# PIC32Square.net
KiCad netlist of a schematic drawn in Altium Designer
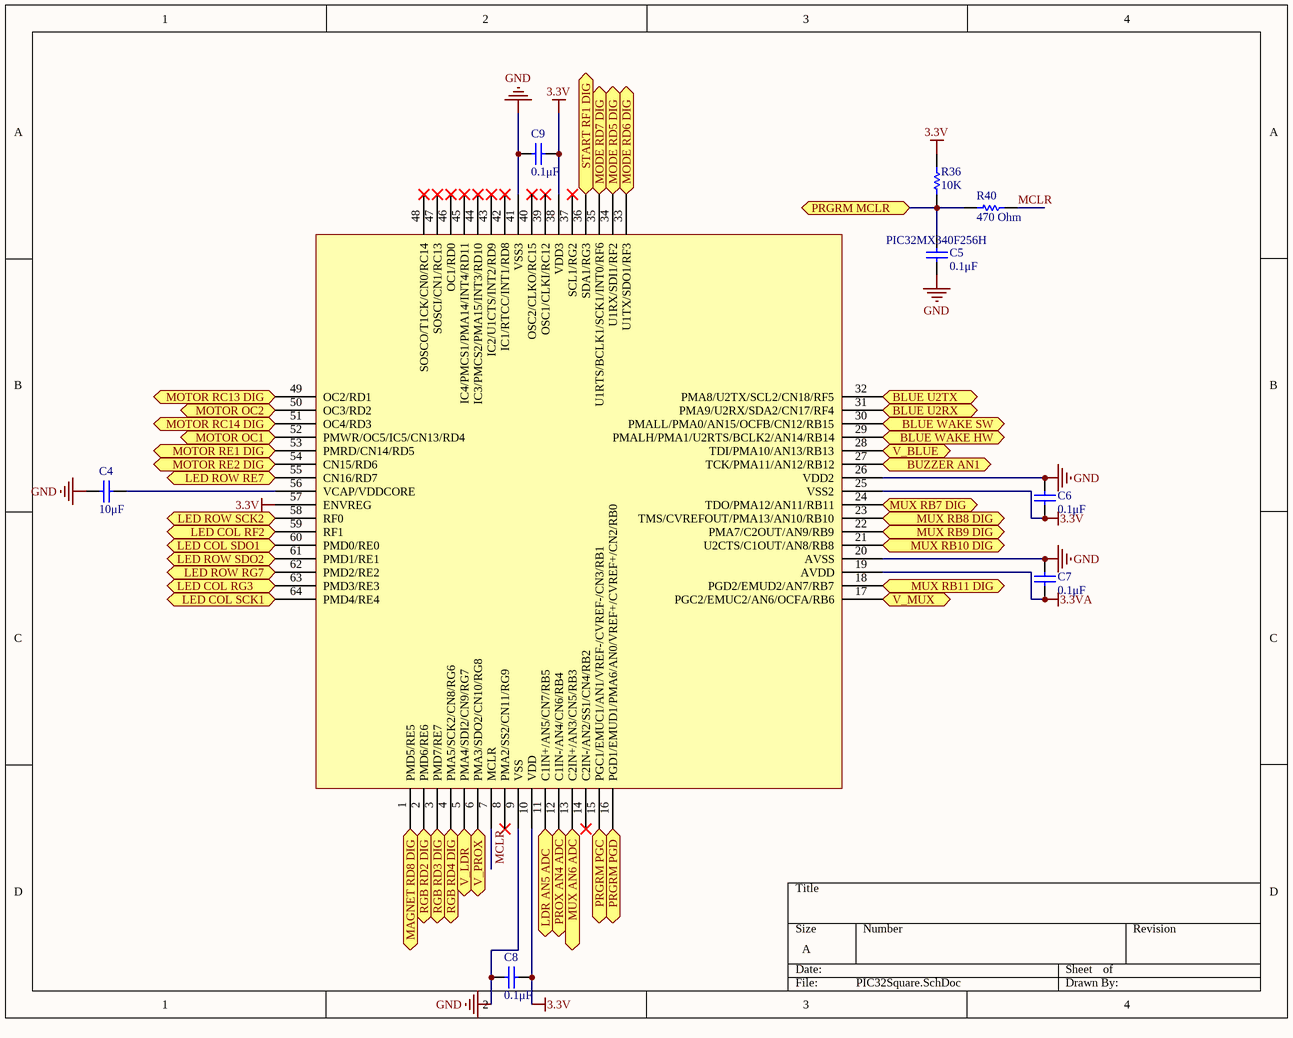
[diagram p0: PIC32Square.SchDoc]

(export (version "E")
  (design (tool "Eeschema 10.0.6"))
  (components
    (comp (ref "C4")
      (value "10μF")
      (footprint "Capacitor")
      (description "Capacitor")
      (fields (field (name "PUBLISHER") "Altium Limited"))
      (libsource (lib "Miscellaneous Devices") (part "Cap"))
    )
    (comp (ref "C5")
      (value "0.1μF")
      (footprint "Capacitor")
      (description "Capacitor")
      (fields (field (name "PUBLISHER") "Altium Limited"))
      (libsource (lib "Miscellaneous Devices") (part "Cap"))
    )
    (comp (ref "C6")
      (value "0.1μF")
      (footprint "Capacitor")
      (description "Capacitor")
      (fields (field (name "PUBLISHER") "Altium Limited"))
      (libsource (lib "Miscellaneous Devices") (part "Cap"))
    )
    (comp (ref "C7")
      (value "0.1μF")
      (footprint "Capacitor")
      (description "Capacitor")
      (fields (field (name "PUBLISHER") "Altium Limited"))
      (libsource (lib "Miscellaneous Devices") (part "Cap"))
    )
    (comp (ref "C8")
      (value "0.1μF")
      (footprint "Capacitor")
      (description "Capacitor")
      (fields (field (name "PUBLISHER") "Altium Limited"))
      (libsource (lib "Miscellaneous Devices") (part "Cap"))
    )
    (comp (ref "C9")
      (value "0.1μF")
      (footprint "Capacitor")
      (description "Capacitor")
      (fields (field (name "PUBLISHER") "Altium Limited"))
      (libsource (lib "Miscellaneous Devices") (part "Cap"))
    )
    (comp (ref "PIC32Square")
      (value "PIC32MX340F256H")
      (footprint "PIC32")
      (libsource (lib "PROBOT_Schema_Library") (part "PIC32square"))
    )
    (comp (ref "R36")
      (value "10K")
      (footprint "Resistor0603")
      (description "Resistor")
      (fields (field (name "PUBLISHER") "Altium Limited"))
      (libsource (lib "Miscellaneous Devices") (part "Res1"))
    )
    (comp (ref "R40")
      (value "470 Ohm")
      (footprint "Resistor0603")
      (description "Resistor")
      (fields (field (name "PUBLISHER") "Altium Limited"))
      (libsource (lib "Miscellaneous Devices") (part "Res1"))
    )
  )
  (nets
    (net (code "1") (name "/BLUE U2RX") (class "Default")
      (node (ref "PIC32Square") (pin "31") (pinfunction "PMA9/U2RX/SDA2/CN17/RF4_31") (pintype "passive"))
    )
    (net (code "2") (name "/BLUE U2TX") (class "Default")
      (node (ref "PIC32Square") (pin "32") (pinfunction "PMA8/U2TX/SCL2/CN18/RF5_32") (pintype "passive"))
    )
    (net (code "3") (name "/BLUE WAKE HW") (class "Default")
      (node (ref "PIC32Square") (pin "29") (pinfunction "PMALH/PMA1/U2RTS/BCLK2/AN14/RB14_29") (pintype "passive"))
    )
    (net (code "4") (name "/BLUE WAKE SW") (class "Default")
      (node (ref "PIC32Square") (pin "30") (pinfunction "PMALL/PMA0/AN15/OCFB/CN12/RB15_30") (pintype "passive"))
    )
    (net (code "5") (name "/BUZZER AN1") (class "Default")
      (node (ref "PIC32Square") (pin "27") (pinfunction "TCK/PMA11/AN12/RB12_27") (pintype "passive"))
    )
    (net (code "6") (name "/LDR AN5 ADC") (class "Default")
      (node (ref "PIC32Square") (pin "11") (pinfunction "C1IN+/AN5/CN7/RB5_11") (pintype "passive"))
    )
    (net (code "7") (name "/LED COL RF2") (class "Default")
      (node (ref "PIC32Square") (pin "59") (pinfunction "RF1_59") (pintype "passive"))
    )
    (net (code "8") (name "/LED COL RG3") (class "Default")
      (node (ref "PIC32Square") (pin "63") (pinfunction "PMD3/RE3_63") (pintype "passive"))
    )
    (net (code "9") (name "/LED COL SCK1") (class "Default")
      (node (ref "PIC32Square") (pin "64") (pinfunction "PMD4/RE4_64") (pintype "passive"))
    )
    (net (code "10") (name "/LED COL SDO1") (class "Default")
      (node (ref "PIC32Square") (pin "60") (pinfunction "PMD0/RE0_60") (pintype "passive"))
    )
    (net (code "11") (name "/LED ROW RE7") (class "Default")
      (node (ref "PIC32Square") (pin "55") (pinfunction "CN16/RD7_55") (pintype "passive"))
    )
    (net (code "12") (name "/LED ROW RG7") (class "Default")
      (node (ref "PIC32Square") (pin "62") (pinfunction "PMD2/RE2_62") (pintype "passive"))
    )
    (net (code "13") (name "/LED ROW SCK2") (class "Default")
      (node (ref "PIC32Square") (pin "58") (pinfunction "RF0_58") (pintype "passive"))
    )
    (net (code "14") (name "/LED ROW SDO2") (class "Default")
      (node (ref "PIC32Square") (pin "61") (pinfunction "PMD1/RE1_61") (pintype "passive"))
    )
    (net (code "15") (name "/MAGNET RD8 DIG") (class "Default")
      (node (ref "PIC32Square") (pin "1") (pinfunction "PMD5/RE5_1") (pintype "passive"))
    )
    (net (code "16") (name "/MCLR") (class "Default")
      (node (ref "PIC32Square") (pin "7") (pinfunction "MCLR_7") (pintype "passive"))
      (node (ref "R40") (pin "1") (pinfunction "1_1") (pintype "passive"))
    )
    (net (code "17") (name "/MODE RD5 DIG") (class "Default")
      (node (ref "PIC32Square") (pin "34") (pinfunction "U1RX/SDI1/RF2_34") (pintype "passive"))
    )
    (net (code "18") (name "/MODE RD6 DIG") (class "Default")
      (node (ref "PIC32Square") (pin "33") (pinfunction "U1TX/SDO1/RF3_33") (pintype "passive"))
    )
    (net (code "19") (name "/MODE RD7 DIG") (class "Default")
      (node (ref "PIC32Square") (pin "35") (pinfunction "U1RTS/BCLK1/SCK1/INT0/RF6_35") (pintype "passive"))
    )
    (net (code "20") (name "/MOTOR OC1") (class "Default")
      (node (ref "PIC32Square") (pin "52") (pinfunction "PMWR/OC5/IC5/CN13/RD4_52") (pintype "passive"))
    )
    (net (code "21") (name "/MOTOR OC2") (class "Default")
      (node (ref "PIC32Square") (pin "50") (pinfunction "OC3/RD2_50") (pintype "passive"))
    )
    (net (code "22") (name "/MOTOR RC13 DIG") (class "Default")
      (node (ref "PIC32Square") (pin "49") (pinfunction "OC2/RD1_49") (pintype "passive"))
    )
    (net (code "23") (name "/MOTOR RC14 DIG") (class "Default")
      (node (ref "PIC32Square") (pin "51") (pinfunction "OC4/RD3_51") (pintype "passive"))
    )
    (net (code "24") (name "/MOTOR RE1 DIG") (class "Default")
      (node (ref "PIC32Square") (pin "53") (pinfunction "PMRD/CN14/RD5_53") (pintype "passive"))
    )
    (net (code "25") (name "/MOTOR RE2 DIG") (class "Default")
      (node (ref "PIC32Square") (pin "54") (pinfunction "CN15/RD6_54") (pintype "passive"))
    )
    (net (code "26") (name "/MUX AN6 ADC") (class "Default")
      (node (ref "PIC32Square") (pin "13") (pinfunction "C2IN+/AN3/CN5/RB3_13") (pintype "passive"))
    )
    (net (code "27") (name "/MUX RB7 DIG") (class "Default")
      (node (ref "PIC32Square") (pin "24") (pinfunction "TDO/PMA12/AN11/RB11_24") (pintype "passive"))
    )
    (net (code "28") (name "/MUX RB8 DIG") (class "Default")
      (node (ref "PIC32Square") (pin "23") (pinfunction "TMS/CVREFOUT/PMA13/AN10/RB10_23") (pintype "passive"))
    )
    (net (code "29") (name "/MUX RB9 DIG") (class "Default")
      (node (ref "PIC32Square") (pin "22") (pinfunction "PMA7/C2OUT/AN9/RB9_22") (pintype "passive"))
    )
    (net (code "30") (name "/MUX RB10 DIG") (class "Default")
      (node (ref "PIC32Square") (pin "21") (pinfunction "U2CTS/C1OUT/AN8/RB8_21") (pintype "passive"))
    )
    (net (code "31") (name "/MUX RB11 DIG") (class "Default")
      (node (ref "PIC32Square") (pin "18") (pinfunction "PGD2/EMUD2/AN7/RB7_18") (pintype "passive"))
    )
    (net (code "32") (name "/PRGRM MCLR") (class "Default")
      (node (ref "C5") (pin "1") (pinfunction "1_1") (pintype "passive"))
      (node (ref "R36") (pin "1") (pinfunction "1_1") (pintype "passive"))
      (node (ref "R40") (pin "2") (pinfunction "2_2") (pintype "passive"))
    )
    (net (code "33") (name "/PRGRM PGC") (class "Default")
      (node (ref "PIC32Square") (pin "15") (pinfunction "PGC1/EMUC1/AN1/VREF-/CVREF-/CN3/RB1_15") (pintype "passive"))
    )
    (net (code "34") (name "/PRGRM PGD") (class "Default")
      (node (ref "PIC32Square") (pin "16") (pinfunction "PGD1/EMUD1/PMA6/AN0/VREF+/CVREF+/CN2/RB0_16") (pintype "passive"))
    )
    (net (code "35") (name "/PROX AN4 ADC") (class "Default")
      (node (ref "PIC32Square") (pin "12") (pinfunction "C1IN-/AN4/CN6/RB4_12") (pintype "passive"))
    )
    (net (code "36") (name "/RGB RD2 DIG") (class "Default")
      (node (ref "PIC32Square") (pin "2") (pinfunction "PMD6/RE6_2") (pintype "passive"))
    )
    (net (code "37") (name "/RGB RD3 DIG") (class "Default")
      (node (ref "PIC32Square") (pin "3") (pinfunction "PMD7/RE7_3") (pintype "passive"))
    )
    (net (code "38") (name "/RGB RD4 DIG") (class "Default")
      (node (ref "PIC32Square") (pin "4") (pinfunction "PMA5/SCK2/CN8/RG6_4") (pintype "passive"))
    )
    (net (code "39") (name "/START RF1 DIG") (class "Default")
      (node (ref "PIC32Square") (pin "36") (pinfunction "SDA1/RG3_36") (pintype "passive"))
    )
    (net (code "40") (name "/V_BLUE") (class "Default")
      (node (ref "PIC32Square") (pin "28") (pinfunction "TDI/PMA10/AN13/RB13_28") (pintype "passive"))
    )
    (net (code "41") (name "/V_LDR") (class "Default")
      (node (ref "PIC32Square") (pin "5") (pinfunction "PMA4/SDI2/CN9/RG7_5") (pintype "passive"))
    )
    (net (code "42") (name "/V_MUX") (class "Default")
      (node (ref "PIC32Square") (pin "17") (pinfunction "PGC2/EMUC2/AN6/OCFA/RB6_17") (pintype "passive"))
    )
    (net (code "43") (name "/V_PROX") (class "Default")
      (node (ref "PIC32Square") (pin "6") (pinfunction "PMA3/SDO2/CN10/RG8_6") (pintype "passive"))
    )
    (net (code "44") (name "3.3V") (class "Default")
      (node (ref "C6") (pin "1") (pinfunction "1_1") (pintype "passive"))
      (node (ref "C8") (pin "1") (pinfunction "1_1") (pintype "passive"))
      (node (ref "C9") (pin "2") (pinfunction "2_2") (pintype "passive"))
      (node (ref "PIC32Square") (pin "10") (pinfunction "VDD_10") (pintype "passive"))
      (node (ref "PIC32Square") (pin "25") (pinfunction "VSS2_25") (pintype "passive"))
      (node (ref "PIC32Square") (pin "38") (pinfunction "VDD3_38") (pintype "passive"))
      (node (ref "PIC32Square") (pin "57") (pinfunction "ENVREG_57") (pintype "passive"))
      (node (ref "R36") (pin "2") (pinfunction "2_2") (pintype "passive"))
    )
    (net (code "45") (name "3.3VA") (class "Default")
      (node (ref "C7") (pin "1") (pinfunction "1_1") (pintype "passive"))
      (node (ref "PIC32Square") (pin "19") (pinfunction "AVDD_19") (pintype "passive"))
    )
    (net (code "46") (name "GND") (class "Default")
      (node (ref "C4") (pin "2") (pinfunction "2_2") (pintype "passive"))
      (node (ref "C5") (pin "2") (pinfunction "2_2") (pintype "passive"))
      (node (ref "C6") (pin "2") (pinfunction "2_2") (pintype "passive"))
      (node (ref "C7") (pin "2") (pinfunction "2_2") (pintype "passive"))
      (node (ref "C8") (pin "2") (pinfunction "2_2") (pintype "passive"))
      (node (ref "C9") (pin "1") (pinfunction "1_1") (pintype "passive"))
      (node (ref "PIC32Square") (pin "20") (pinfunction "AVSS_20") (pintype "passive"))
      (node (ref "PIC32Square") (pin "26") (pinfunction "VDD2_26") (pintype "passive"))
      (node (ref "PIC32Square") (pin "41") (pinfunction "VSS3_41") (pintype "passive"))
      (node (ref "PIC32Square") (pin "9") (pinfunction "VSS_9") (pintype "passive"))
    )
    (net (code "47") (name "Net-(PIC32Square-VCAP{slash}VDDCORE)") (class "Default")
      (node (ref "C4") (pin "1") (pinfunction "1_1") (pintype "passive"))
      (node (ref "PIC32Square") (pin "56") (pinfunction "VCAP/VDDCORE_56") (pintype "passive"))
    )
    (net (code "48") (name "unconnected-(PIC32Square-C2IN-{slash}AN2{slash}SS1{slash}CN4{slash}RB2-Pad14)") (class "Default")
      (node (ref "PIC32Square") (pin "14") (pinfunction "C2IN-/AN2/SS1/CN4/RB2_14") (pintype "passive+no_connect"))
    )
    (net (code "49") (name "unconnected-(PIC32Square-IC1{slash}RTCC{slash}INT1{slash}RD8-Pad42)") (class "Default")
      (node (ref "PIC32Square") (pin "42") (pinfunction "IC1/RTCC/INT1/RD8_42") (pintype "passive+no_connect"))
    )
    (net (code "50") (name "unconnected-(PIC32Square-IC2{slash}U1CTS{slash}INT2{slash}RD9-Pad43)") (class "Default")
      (node (ref "PIC32Square") (pin "43") (pinfunction "IC2/U1CTS/INT2/RD9_43") (pintype "passive+no_connect"))
    )
    (net (code "51") (name "unconnected-(PIC32Square-IC3{slash}PMCS2{slash}PMA15{slash}INT3{slash}RD10-Pad44)") (class "Default")
      (node (ref "PIC32Square") (pin "44") (pinfunction "IC3/PMCS2/PMA15/INT3/RD10_44") (pintype "passive+no_connect"))
    )
    (net (code "52") (name "unconnected-(PIC32Square-IC4{slash}PMCS1{slash}PMA14{slash}INT4{slash}RD11-Pad45)") (class "Default")
      (node (ref "PIC32Square") (pin "45") (pinfunction "IC4/PMCS1/PMA14/INT4/RD11_45") (pintype "passive+no_connect"))
    )
    (net (code "53") (name "unconnected-(PIC32Square-OC1{slash}RD0-Pad46)") (class "Default")
      (node (ref "PIC32Square") (pin "46") (pinfunction "OC1/RD0_46") (pintype "passive+no_connect"))
    )
    (net (code "54") (name "unconnected-(PIC32Square-OSC1{slash}CLKI{slash}RC12-Pad39)") (class "Default")
      (node (ref "PIC32Square") (pin "39") (pinfunction "OSC1/CLKI/RC12_39") (pintype "passive+no_connect"))
    )
    (net (code "55") (name "unconnected-(PIC32Square-OSC2{slash}CLKO{slash}RC15-Pad40)") (class "Default")
      (node (ref "PIC32Square") (pin "40") (pinfunction "OSC2/CLKO/RC15_40") (pintype "passive+no_connect"))
    )
    (net (code "56") (name "unconnected-(PIC32Square-PMA2{slash}SS2{slash}CN11{slash}RG9-Pad8)") (class "Default")
      (node (ref "PIC32Square") (pin "8") (pinfunction "PMA2/SS2/CN11/RG9_8") (pintype "passive+no_connect"))
    )
    (net (code "57") (name "unconnected-(PIC32Square-SCL1{slash}RG2-Pad37)") (class "Default")
      (node (ref "PIC32Square") (pin "37") (pinfunction "SCL1/RG2_37") (pintype "passive+no_connect"))
    )
    (net (code "58") (name "unconnected-(PIC32Square-SOSCI{slash}CN1{slash}RC13-Pad47)") (class "Default")
      (node (ref "PIC32Square") (pin "47") (pinfunction "SOSCI/CN1/RC13_47") (pintype "passive+no_connect"))
    )
    (net (code "59") (name "unconnected-(PIC32Square-SOSCO{slash}T1CK{slash}CN0{slash}RC14-Pad48)") (class "Default")
      (node (ref "PIC32Square") (pin "48") (pinfunction "SOSCO/T1CK/CN0/RC14_48") (pintype "passive+no_connect"))
    )
  )
)
